# Nixie_Board.net
KiCad netlist of a schematic drawn in EAGLE
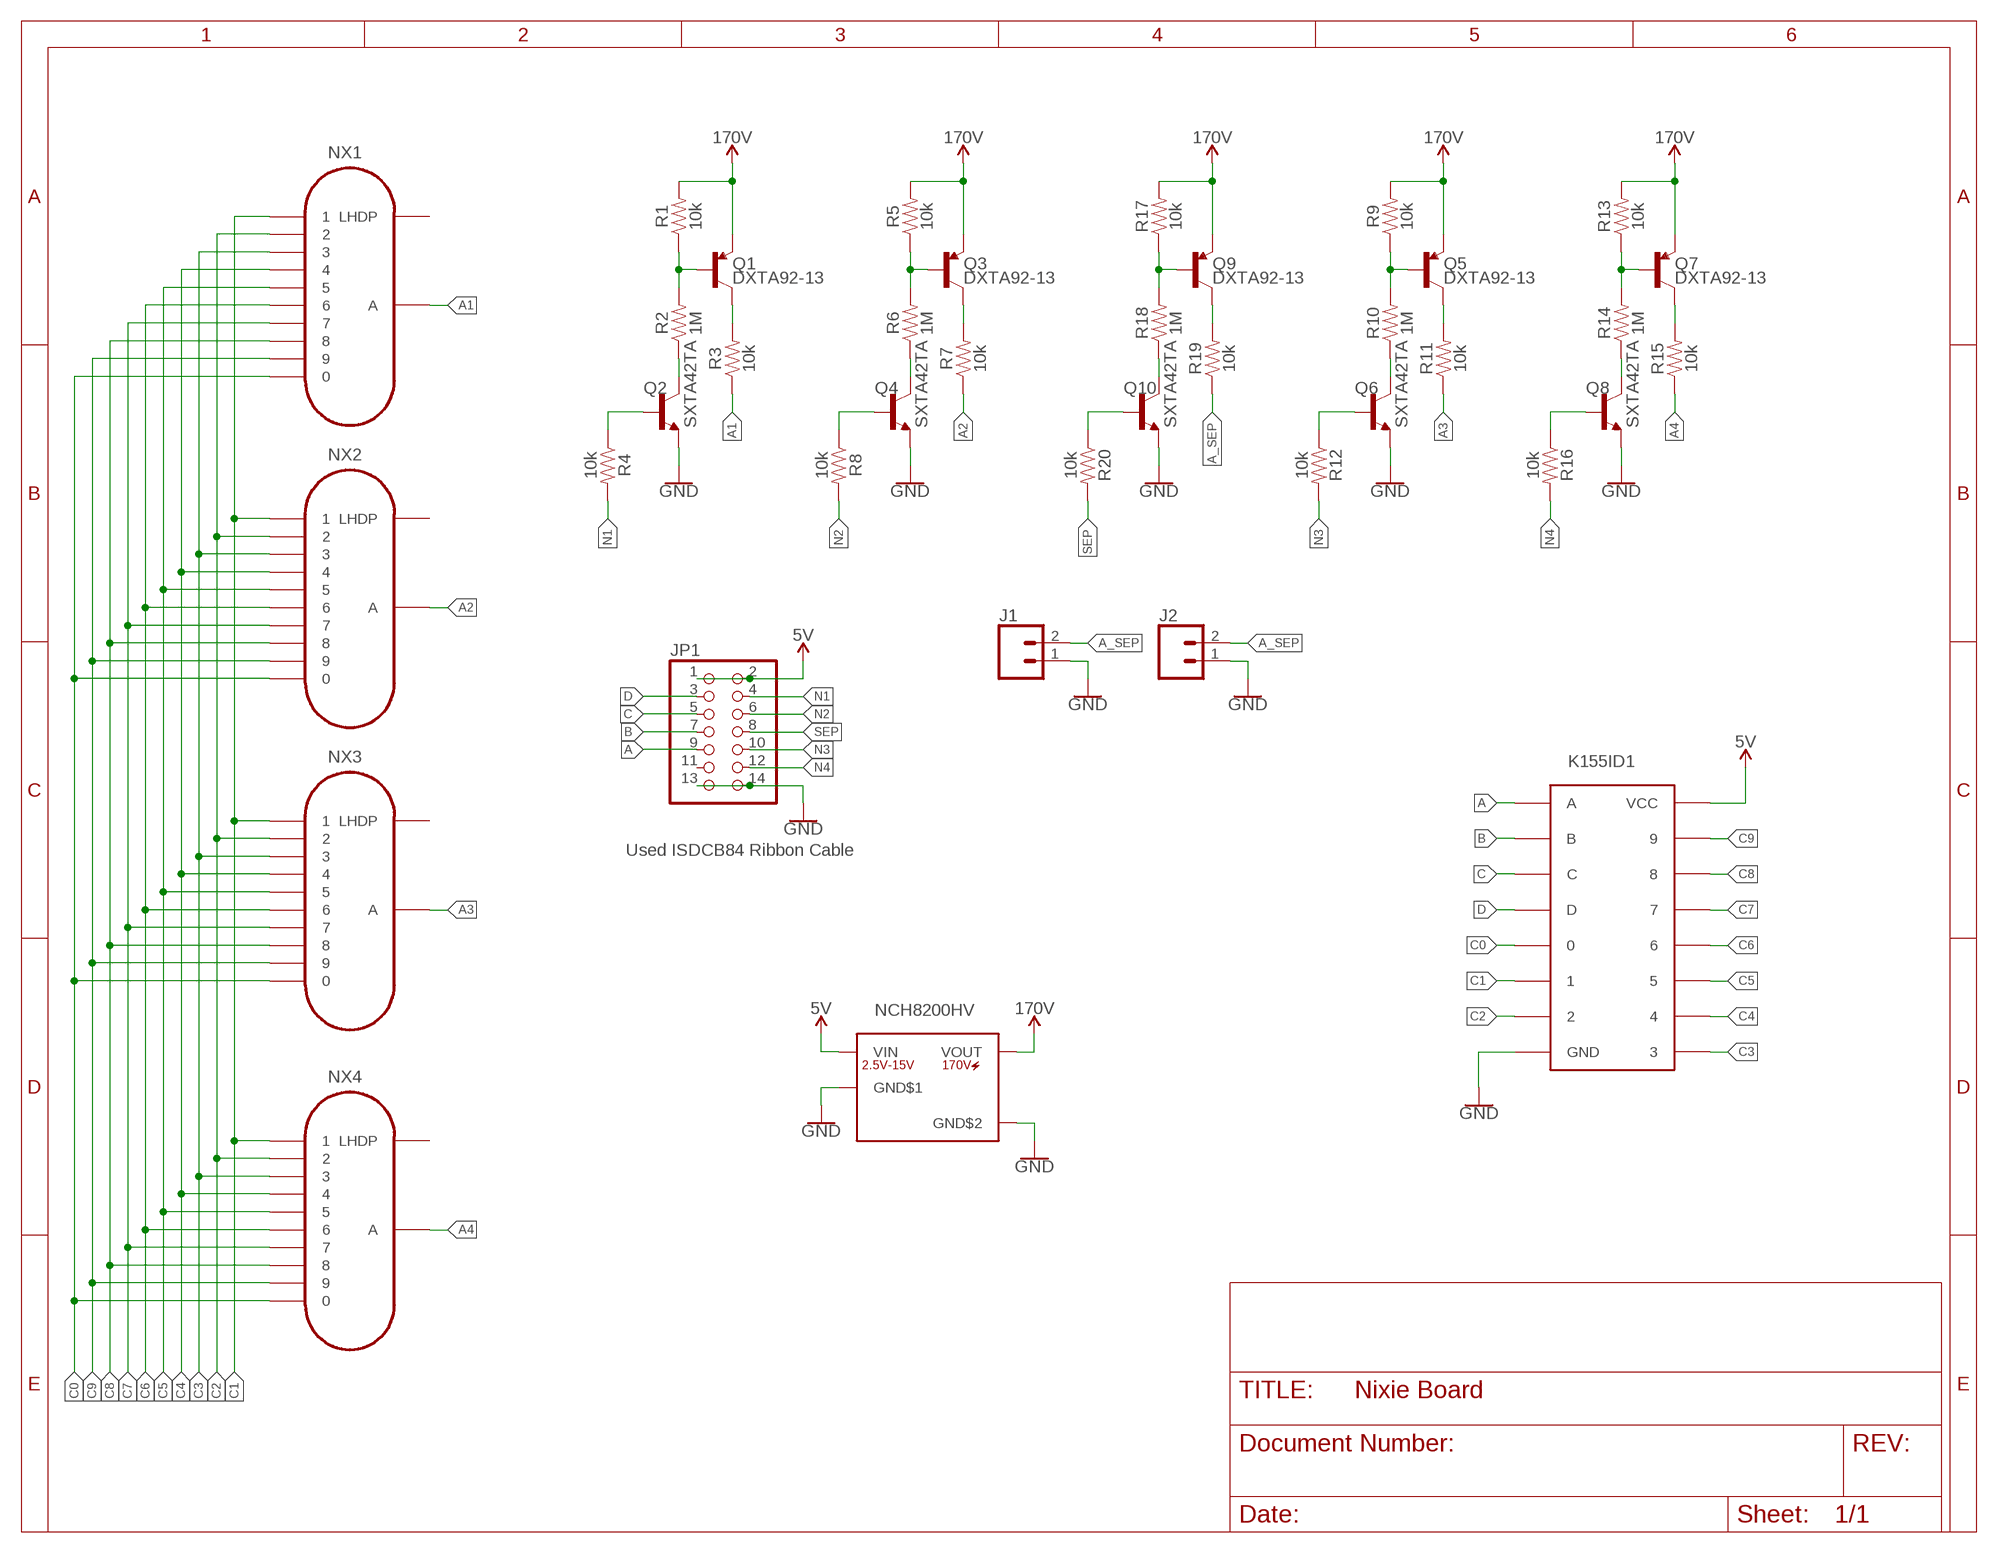
[diagram p0: schematic, sheet 1]

(export (version "E")
  (design (tool "Eeschema 10.0.6"))
  (components
    (comp (ref "J1")
      (value "CONN_02")
      (footprint "eagle-import:1X02")
      (fields (field (name "MPN") "INS-1"))
      (libsource (lib "eagle-import") (part "CONN_02"))
    )
    (comp (ref "J2")
      (value "CONN_02")
      (footprint "eagle-import:1X02")
      (fields (field (name "MPN") "INS-1"))
      (libsource (lib "eagle-import") (part "CONN_02"))
    )
    (comp (ref "JP1")
      (value "PINHD-2X7")
      (footprint "eagle-import:2X07")
      (fields (field (name "MPN") "30314-6002HB"))
      (libsource (lib "eagle-import") (part "PINHD-2X7"))
    )
    (comp (ref "NX1")
      (value "IN-12BNOHOLE")
      (footprint "eagle-import:IN-12-DSUB-NOHOLE")
      (fields (field (name "MPN") "IN-12B"))
      (libsource (lib "eagle-import") (part "IN-12BNOHOLE"))
    )
    (comp (ref "NX2")
      (value "IN-12BNOHOLE")
      (footprint "eagle-import:IN-12-DSUB-NOHOLE")
      (fields (field (name "MPN") "IN-12B"))
      (libsource (lib "eagle-import") (part "IN-12BNOHOLE"))
    )
    (comp (ref "NX3")
      (value "IN-12BNOHOLE")
      (footprint "eagle-import:IN-12-DSUB-NOHOLE")
      (fields (field (name "MPN") "IN-12B"))
      (libsource (lib "eagle-import") (part "IN-12BNOHOLE"))
    )
    (comp (ref "NX4")
      (value "IN-12BNOHOLE")
      (footprint "eagle-import:IN-12-DSUB-NOHOLE")
      (fields (field (name "MPN") "IN-12B"))
      (libsource (lib "eagle-import") (part "IN-12BNOHOLE"))
    )
    (comp (ref "Q1")
      (value "DXTA92-13")
      (footprint "eagle-import:DXTA9213")
      (fields (field (name "MOUSER_PART_NUMBER") "621-DXTA92-13"))
      (libsource (lib "eagle-import") (part "DXTA92-13"))
    )
    (comp (ref "Q2")
      (value "SXTA42TA")
      (footprint "eagle-import:SXTA42TA")
      (fields (field (name "MOUSER_PART_NUMBER") "522-SXTA42TA"))
      (libsource (lib "eagle-import") (part "SXTA42TA"))
    )
    (comp (ref "Q3")
      (value "DXTA92-13")
      (footprint "eagle-import:DXTA9213")
      (fields (field (name "MOUSER_PART_NUMBER") "621-DXTA92-13"))
      (libsource (lib "eagle-import") (part "DXTA92-13"))
    )
    (comp (ref "Q4")
      (value "SXTA42TA")
      (footprint "eagle-import:SXTA42TA")
      (fields (field (name "MOUSER_PART_NUMBER") "522-SXTA42TA"))
      (libsource (lib "eagle-import") (part "SXTA42TA"))
    )
    (comp (ref "Q5")
      (value "DXTA92-13")
      (footprint "eagle-import:DXTA9213")
      (fields (field (name "MOUSER_PART_NUMBER") "621-DXTA92-13"))
      (libsource (lib "eagle-import") (part "DXTA92-13"))
    )
    (comp (ref "Q6")
      (value "SXTA42TA")
      (footprint "eagle-import:SXTA42TA")
      (fields (field (name "MOUSER_PART_NUMBER") "522-SXTA42TA"))
      (libsource (lib "eagle-import") (part "SXTA42TA"))
    )
    (comp (ref "Q7")
      (value "DXTA92-13")
      (footprint "eagle-import:DXTA9213")
      (fields (field (name "MOUSER_PART_NUMBER") "621-DXTA92-13"))
      (libsource (lib "eagle-import") (part "DXTA92-13"))
    )
    (comp (ref "Q8")
      (value "SXTA42TA")
      (footprint "eagle-import:SXTA42TA")
      (fields (field (name "MOUSER_PART_NUMBER") "522-SXTA42TA"))
      (libsource (lib "eagle-import") (part "SXTA42TA"))
    )
    (comp (ref "Q9")
      (value "DXTA92-13")
      (footprint "eagle-import:DXTA9213")
      (fields (field (name "MOUSER_PART_NUMBER") "621-DXTA92-13"))
      (libsource (lib "eagle-import") (part "DXTA92-13"))
    )
    (comp (ref "Q10")
      (value "SXTA42TA")
      (footprint "eagle-import:SXTA42TA")
      (fields (field (name "MOUSER_PART_NUMBER") "522-SXTA42TA"))
      (libsource (lib "eagle-import") (part "SXTA42TA"))
    )
    (comp (ref "R1")
      (value "10k")
      (footprint "eagle-import:0603")
      (fields (field (name "MPN") "ESR03EZPJ103"))
      (libsource (lib "eagle-import") (part "10KOHM-0603-1/10W-1%"))
    )
    (comp (ref "R2")
      (value "1M")
      (footprint "eagle-import:0603")
      (fields (field (name "MPN") "ERJ-3EKF1004V"))
      (libsource (lib "eagle-import") (part "1MOHM-0603-1/4W-5%"))
    )
    (comp (ref "R3")
      (value "10k")
      (footprint "eagle-import:0603")
      (fields (field (name "MPN") "ESR03EZPJ103"))
      (libsource (lib "eagle-import") (part "10KOHM-0603-1/10W-1%"))
    )
    (comp (ref "R4")
      (value "10k")
      (footprint "eagle-import:0603")
      (fields (field (name "MPN") "ESR03EZPJ103"))
      (libsource (lib "eagle-import") (part "10KOHM-0603-1/10W-1%"))
    )
    (comp (ref "R5")
      (value "10k")
      (footprint "eagle-import:0603")
      (fields (field (name "MPN") "ESR03EZPJ103"))
      (libsource (lib "eagle-import") (part "10KOHM-0603-1/10W-1%"))
    )
    (comp (ref "R6")
      (value "1M")
      (footprint "eagle-import:0603")
      (fields (field (name "MPN") "ERJ-3EKF1004V"))
      (libsource (lib "eagle-import") (part "1MOHM-0603-1/4W-5%"))
    )
    (comp (ref "R7")
      (value "10k")
      (footprint "eagle-import:0603")
      (fields (field (name "MPN") "ESR03EZPJ103"))
      (libsource (lib "eagle-import") (part "10KOHM-0603-1/10W-1%"))
    )
    (comp (ref "R8")
      (value "10k")
      (footprint "eagle-import:0603")
      (fields (field (name "MPN") "ESR03EZPJ103"))
      (libsource (lib "eagle-import") (part "10KOHM-0603-1/10W-1%"))
    )
    (comp (ref "R9")
      (value "10k")
      (footprint "eagle-import:0603")
      (fields (field (name "MPN") "ESR03EZPJ103"))
      (libsource (lib "eagle-import") (part "10KOHM-0603-1/10W-1%"))
    )
    (comp (ref "R10")
      (value "1M")
      (footprint "eagle-import:0603")
      (fields (field (name "MPN") "ERJ-3EKF1004V"))
      (libsource (lib "eagle-import") (part "1MOHM-0603-1/4W-5%"))
    )
    (comp (ref "R11")
      (value "10k")
      (footprint "eagle-import:0603")
      (fields (field (name "MPN") "ESR03EZPJ103"))
      (libsource (lib "eagle-import") (part "10KOHM-0603-1/10W-1%"))
    )
    (comp (ref "R12")
      (value "10k")
      (footprint "eagle-import:0603")
      (fields (field (name "MPN") "ESR03EZPJ103"))
      (libsource (lib "eagle-import") (part "10KOHM-0603-1/10W-1%"))
    )
    (comp (ref "R13")
      (value "10k")
      (footprint "eagle-import:0603")
      (fields (field (name "MPN") "ESR03EZPJ103"))
      (libsource (lib "eagle-import") (part "10KOHM-0603-1/10W-1%"))
    )
    (comp (ref "R14")
      (value "1M")
      (footprint "eagle-import:0603")
      (fields (field (name "MPN") "ERJ-3EKF1004V"))
      (libsource (lib "eagle-import") (part "1MOHM-0603-1/4W-5%"))
    )
    (comp (ref "R15")
      (value "10k")
      (footprint "eagle-import:0603")
      (fields (field (name "MPN") "ESR03EZPJ103"))
      (libsource (lib "eagle-import") (part "10KOHM-0603-1/10W-1%"))
    )
    (comp (ref "R16")
      (value "10k")
      (footprint "eagle-import:0603")
      (fields (field (name "MPN") "ESR03EZPJ103"))
      (libsource (lib "eagle-import") (part "10KOHM-0603-1/10W-1%"))
    )
    (comp (ref "R17")
      (value "10k")
      (footprint "eagle-import:0603")
      (fields (field (name "MPN") "ESR03EZPJ103"))
      (libsource (lib "eagle-import") (part "10KOHM-0603-1/10W-1%"))
    )
    (comp (ref "R18")
      (value "1M")
      (footprint "eagle-import:0603")
      (fields (field (name "MPN") "ERJ-3EKF1004V"))
      (libsource (lib "eagle-import") (part "1MOHM-0603-1/4W-5%"))
    )
    (comp (ref "R19")
      (value "10k")
      (footprint "eagle-import:0603")
      (fields (field (name "MPN") "ESR03EZPJ103"))
      (libsource (lib "eagle-import") (part "10KOHM-0603-1/10W-1%"))
    )
    (comp (ref "R20")
      (value "10k")
      (footprint "eagle-import:0603")
      (fields (field (name "MPN") "ESR03EZPJ103"))
      (libsource (lib "eagle-import") (part "10KOHM-0603-1/10W-1%"))
    )
    (comp (ref "U$1")
      (value "K155ID1")
      (footprint "eagle-import:DIP16")
      (libsource (lib "eagle-import") (part "K155ID1"))
    )
    (comp (ref "U$2")
      (value "NCH8200HV")
      (footprint "eagle-import:NCH8200HV")
      (libsource (lib "eagle-import") (part "NCH8200HV"))
    )
  )
  (nets
    (net (code "1") (name "5V") (class "Default")
      (node (ref "JP1") (pin "1") (pinfunction "1_1") (pintype "passive"))
      (node (ref "JP1") (pin "2") (pinfunction "2_2") (pintype "passive"))
      (node (ref "U$1") (pin "5") (pinfunction "VCC_5") (pintype "power_in"))
      (node (ref "U$2") (pin "P$1") (pinfunction "VIN_P$1") (pintype "power_in"))
    )
    (net (code "2") (name "170V") (class "Default")
      (node (ref "Q1") (pin "3") (pinfunction "E_3") (pintype "passive"))
      (node (ref "Q3") (pin "3") (pinfunction "E_3") (pintype "passive"))
      (node (ref "Q5") (pin "3") (pinfunction "E_3") (pintype "passive"))
      (node (ref "Q7") (pin "3") (pinfunction "E_3") (pintype "passive"))
      (node (ref "Q9") (pin "3") (pinfunction "E_3") (pintype "passive"))
      (node (ref "R1") (pin "2") (pinfunction "2_2") (pintype "passive"))
      (node (ref "R13") (pin "2") (pinfunction "2_2") (pintype "passive"))
      (node (ref "R17") (pin "2") (pinfunction "2_2") (pintype "passive"))
      (node (ref "R5") (pin "2") (pinfunction "2_2") (pintype "passive"))
      (node (ref "R9") (pin "2") (pinfunction "2_2") (pintype "passive"))
      (node (ref "U$2") (pin "P$4") (pinfunction "VOUT_P$4") (pintype "power_in"))
    )
    (net (code "3") (name "A") (class "Default")
      (node (ref "JP1") (pin "9") (pinfunction "9_9") (pintype "passive"))
      (node (ref "U$1") (pin "3") (pinfunction "A_3") (pintype "input"))
    )
    (net (code "4") (name "A1") (class "Default")
      (node (ref "NX1") (pin "A") (pinfunction "A_A") (pintype "bidirectional"))
      (node (ref "R3") (pin "1") (pinfunction "1_1") (pintype "passive"))
    )
    (net (code "5") (name "A2") (class "Default")
      (node (ref "NX2") (pin "A") (pinfunction "A_A") (pintype "bidirectional"))
      (node (ref "R7") (pin "1") (pinfunction "1_1") (pintype "passive"))
    )
    (net (code "6") (name "A3") (class "Default")
      (node (ref "NX3") (pin "A") (pinfunction "A_A") (pintype "bidirectional"))
      (node (ref "R11") (pin "1") (pinfunction "1_1") (pintype "passive"))
    )
    (net (code "7") (name "A4") (class "Default")
      (node (ref "NX4") (pin "A") (pinfunction "A_A") (pintype "bidirectional"))
      (node (ref "R15") (pin "1") (pinfunction "1_1") (pintype "passive"))
    )
    (net (code "8") (name "A_SEP") (class "Default")
      (node (ref "J1") (pin "2") (pinfunction "2_2") (pintype "passive"))
      (node (ref "J2") (pin "2") (pinfunction "2_2") (pintype "passive"))
      (node (ref "R19") (pin "1") (pinfunction "1_1") (pintype "passive"))
    )
    (net (code "9") (name "B") (class "Default")
      (node (ref "JP1") (pin "7") (pinfunction "7_7") (pintype "passive"))
      (node (ref "U$1") (pin "6") (pinfunction "B_6") (pintype "input"))
    )
    (net (code "10") (name "C") (class "Default")
      (node (ref "JP1") (pin "5") (pinfunction "5_5") (pintype "passive"))
      (node (ref "U$1") (pin "7") (pinfunction "C_7") (pintype "input"))
    )
    (net (code "11") (name "C0") (class "Default")
      (node (ref "NX1") (pin "0") (pinfunction "0_0") (pintype "bidirectional"))
      (node (ref "NX2") (pin "0") (pinfunction "0_0") (pintype "bidirectional"))
      (node (ref "NX3") (pin "0") (pinfunction "0_0") (pintype "bidirectional"))
      (node (ref "NX4") (pin "0") (pinfunction "0_0") (pintype "bidirectional"))
      (node (ref "U$1") (pin "16") (pinfunction "0_16") (pintype "output"))
    )
    (net (code "12") (name "C1") (class "Default")
      (node (ref "NX1") (pin "1") (pinfunction "1_1") (pintype "bidirectional"))
      (node (ref "NX2") (pin "1") (pinfunction "1_1") (pintype "bidirectional"))
      (node (ref "NX3") (pin "1") (pinfunction "1_1") (pintype "bidirectional"))
      (node (ref "NX4") (pin "1") (pinfunction "1_1") (pintype "bidirectional"))
      (node (ref "U$1") (pin "15") (pinfunction "1_15") (pintype "output"))
    )
    (net (code "13") (name "C2") (class "Default")
      (node (ref "NX1") (pin "2") (pinfunction "2_2") (pintype "bidirectional"))
      (node (ref "NX2") (pin "2") (pinfunction "2_2") (pintype "bidirectional"))
      (node (ref "NX3") (pin "2") (pinfunction "2_2") (pintype "bidirectional"))
      (node (ref "NX4") (pin "2") (pinfunction "2_2") (pintype "bidirectional"))
      (node (ref "U$1") (pin "8") (pinfunction "2_8") (pintype "output"))
    )
    (net (code "14") (name "C3") (class "Default")
      (node (ref "NX1") (pin "3") (pinfunction "3_3") (pintype "bidirectional"))
      (node (ref "NX2") (pin "3") (pinfunction "3_3") (pintype "bidirectional"))
      (node (ref "NX3") (pin "3") (pinfunction "3_3") (pintype "bidirectional"))
      (node (ref "NX4") (pin "3") (pinfunction "3_3") (pintype "bidirectional"))
      (node (ref "U$1") (pin "9") (pinfunction "3_9") (pintype "output"))
    )
    (net (code "15") (name "C4") (class "Default")
      (node (ref "NX1") (pin "4") (pinfunction "4_4") (pintype "bidirectional"))
      (node (ref "NX2") (pin "4") (pinfunction "4_4") (pintype "bidirectional"))
      (node (ref "NX3") (pin "4") (pinfunction "4_4") (pintype "bidirectional"))
      (node (ref "NX4") (pin "4") (pinfunction "4_4") (pintype "bidirectional"))
      (node (ref "U$1") (pin "13") (pinfunction "4_13") (pintype "output"))
    )
    (net (code "16") (name "C5") (class "Default")
      (node (ref "NX1") (pin "5") (pinfunction "5_5") (pintype "bidirectional"))
      (node (ref "NX2") (pin "5") (pinfunction "5_5") (pintype "bidirectional"))
      (node (ref "NX3") (pin "5") (pinfunction "5_5") (pintype "bidirectional"))
      (node (ref "NX4") (pin "5") (pinfunction "5_5") (pintype "bidirectional"))
      (node (ref "U$1") (pin "14") (pinfunction "5_14") (pintype "output"))
    )
    (net (code "17") (name "C6") (class "Default")
      (node (ref "NX1") (pin "6") (pinfunction "6_6") (pintype "bidirectional"))
      (node (ref "NX2") (pin "6") (pinfunction "6_6") (pintype "bidirectional"))
      (node (ref "NX3") (pin "6") (pinfunction "6_6") (pintype "bidirectional"))
      (node (ref "NX4") (pin "6") (pinfunction "6_6") (pintype "bidirectional"))
      (node (ref "U$1") (pin "11") (pinfunction "6_11") (pintype "output"))
    )
    (net (code "18") (name "C7") (class "Default")
      (node (ref "NX1") (pin "7") (pinfunction "7_7") (pintype "bidirectional"))
      (node (ref "NX2") (pin "7") (pinfunction "7_7") (pintype "bidirectional"))
      (node (ref "NX3") (pin "7") (pinfunction "7_7") (pintype "bidirectional"))
      (node (ref "NX4") (pin "7") (pinfunction "7_7") (pintype "bidirectional"))
      (node (ref "U$1") (pin "10") (pinfunction "7_10") (pintype "output"))
    )
    (net (code "19") (name "C8") (class "Default")
      (node (ref "NX1") (pin "8") (pinfunction "8_8") (pintype "bidirectional"))
      (node (ref "NX2") (pin "8") (pinfunction "8_8") (pintype "bidirectional"))
      (node (ref "NX3") (pin "8") (pinfunction "8_8") (pintype "bidirectional"))
      (node (ref "NX4") (pin "8") (pinfunction "8_8") (pintype "bidirectional"))
      (node (ref "U$1") (pin "1") (pinfunction "8_1") (pintype "output"))
    )
    (net (code "20") (name "C9") (class "Default")
      (node (ref "NX1") (pin "9") (pinfunction "9_9") (pintype "bidirectional"))
      (node (ref "NX2") (pin "9") (pinfunction "9_9") (pintype "bidirectional"))
      (node (ref "NX3") (pin "9") (pinfunction "9_9") (pintype "bidirectional"))
      (node (ref "NX4") (pin "9") (pinfunction "9_9") (pintype "bidirectional"))
      (node (ref "U$1") (pin "2") (pinfunction "9_2") (pintype "output"))
    )
    (net (code "21") (name "D") (class "Default")
      (node (ref "JP1") (pin "3") (pinfunction "3_3") (pintype "passive"))
      (node (ref "U$1") (pin "4") (pinfunction "D_4") (pintype "input"))
    )
    (net (code "22") (name "GND") (class "Default")
      (node (ref "J1") (pin "1") (pinfunction "1_1") (pintype "passive"))
      (node (ref "J2") (pin "1") (pinfunction "1_1") (pintype "passive"))
      (node (ref "JP1") (pin "13") (pinfunction "13_13") (pintype "passive"))
      (node (ref "JP1") (pin "14") (pinfunction "14_14") (pintype "passive"))
      (node (ref "Q10") (pin "3") (pinfunction "E_3") (pintype "passive"))
      (node (ref "Q2") (pin "3") (pinfunction "E_3") (pintype "passive"))
      (node (ref "Q4") (pin "3") (pinfunction "E_3") (pintype "passive"))
      (node (ref "Q6") (pin "3") (pinfunction "E_3") (pintype "passive"))
      (node (ref "Q8") (pin "3") (pinfunction "E_3") (pintype "passive"))
      (node (ref "U$1") (pin "12") (pinfunction "GND_12") (pintype "power_in"))
      (node (ref "U$2") (pin "P$2") (pinfunction "GND$1_P$2") (pintype "power_in"))
      (node (ref "U$2") (pin "P$3") (pinfunction "GND$2_P$3") (pintype "power_in"))
    )
    (net (code "23") (name "N1") (class "Default")
      (node (ref "JP1") (pin "4") (pinfunction "4_4") (pintype "passive"))
      (node (ref "R4") (pin "2") (pinfunction "2_2") (pintype "passive"))
    )
    (net (code "24") (name "N2") (class "Default")
      (node (ref "JP1") (pin "6") (pinfunction "6_6") (pintype "passive"))
      (node (ref "R8") (pin "2") (pinfunction "2_2") (pintype "passive"))
    )
    (net (code "25") (name "N3") (class "Default")
      (node (ref "JP1") (pin "10") (pinfunction "10_10") (pintype "passive"))
      (node (ref "R12") (pin "2") (pinfunction "2_2") (pintype "passive"))
    )
    (net (code "26") (name "N4") (class "Default")
      (node (ref "JP1") (pin "12") (pinfunction "12_12") (pintype "passive"))
      (node (ref "R16") (pin "2") (pinfunction "2_2") (pintype "passive"))
    )
    (net (code "27") (name "Net-(Q1-B)") (class "Default")
      (node (ref "Q1") (pin "1") (pinfunction "B_1") (pintype "passive"))
      (node (ref "R1") (pin "1") (pinfunction "1_1") (pintype "passive"))
      (node (ref "R2") (pin "2") (pinfunction "2_2") (pintype "passive"))
    )
    (net (code "28") (name "Net-(Q1-C)") (class "Default")
      (node (ref "Q1") (pin "2") (pinfunction "C_2") (pintype "passive"))
      (node (ref "R3") (pin "2") (pinfunction "2_2") (pintype "passive"))
    )
    (net (code "29") (name "Net-(Q2-B)") (class "Default")
      (node (ref "Q2") (pin "1") (pinfunction "B_1") (pintype "passive"))
      (node (ref "R4") (pin "1") (pinfunction "1_1") (pintype "passive"))
    )
    (net (code "30") (name "Net-(Q2-C)") (class "Default")
      (node (ref "Q2") (pin "2") (pinfunction "C_2") (pintype "passive"))
      (node (ref "R2") (pin "1") (pinfunction "1_1") (pintype "passive"))
    )
    (net (code "31") (name "Net-(Q3-B)") (class "Default")
      (node (ref "Q3") (pin "1") (pinfunction "B_1") (pintype "passive"))
      (node (ref "R5") (pin "1") (pinfunction "1_1") (pintype "passive"))
      (node (ref "R6") (pin "2") (pinfunction "2_2") (pintype "passive"))
    )
    (net (code "32") (name "Net-(Q3-C)") (class "Default")
      (node (ref "Q3") (pin "2") (pinfunction "C_2") (pintype "passive"))
      (node (ref "R7") (pin "2") (pinfunction "2_2") (pintype "passive"))
    )
    (net (code "33") (name "Net-(Q4-B)") (class "Default")
      (node (ref "Q4") (pin "1") (pinfunction "B_1") (pintype "passive"))
      (node (ref "R8") (pin "1") (pinfunction "1_1") (pintype "passive"))
    )
    (net (code "34") (name "Net-(Q4-C)") (class "Default")
      (node (ref "Q4") (pin "2") (pinfunction "C_2") (pintype "passive"))
      (node (ref "R6") (pin "1") (pinfunction "1_1") (pintype "passive"))
    )
    (net (code "35") (name "Net-(Q5-B)") (class "Default")
      (node (ref "Q5") (pin "1") (pinfunction "B_1") (pintype "passive"))
      (node (ref "R10") (pin "2") (pinfunction "2_2") (pintype "passive"))
      (node (ref "R9") (pin "1") (pinfunction "1_1") (pintype "passive"))
    )
    (net (code "36") (name "Net-(Q5-C)") (class "Default")
      (node (ref "Q5") (pin "2") (pinfunction "C_2") (pintype "passive"))
      (node (ref "R11") (pin "2") (pinfunction "2_2") (pintype "passive"))
    )
    (net (code "37") (name "Net-(Q6-B)") (class "Default")
      (node (ref "Q6") (pin "1") (pinfunction "B_1") (pintype "passive"))
      (node (ref "R12") (pin "1") (pinfunction "1_1") (pintype "passive"))
    )
    (net (code "38") (name "Net-(Q6-C)") (class "Default")
      (node (ref "Q6") (pin "2") (pinfunction "C_2") (pintype "passive"))
      (node (ref "R10") (pin "1") (pinfunction "1_1") (pintype "passive"))
    )
    (net (code "39") (name "Net-(Q7-B)") (class "Default")
      (node (ref "Q7") (pin "1") (pinfunction "B_1") (pintype "passive"))
      (node (ref "R13") (pin "1") (pinfunction "1_1") (pintype "passive"))
      (node (ref "R14") (pin "2") (pinfunction "2_2") (pintype "passive"))
    )
    (net (code "40") (name "Net-(Q7-C)") (class "Default")
      (node (ref "Q7") (pin "2") (pinfunction "C_2") (pintype "passive"))
      (node (ref "R15") (pin "2") (pinfunction "2_2") (pintype "passive"))
    )
    (net (code "41") (name "Net-(Q8-B)") (class "Default")
      (node (ref "Q8") (pin "1") (pinfunction "B_1") (pintype "passive"))
      (node (ref "R16") (pin "1") (pinfunction "1_1") (pintype "passive"))
    )
    (net (code "42") (name "Net-(Q8-C)") (class "Default")
      (node (ref "Q8") (pin "2") (pinfunction "C_2") (pintype "passive"))
      (node (ref "R14") (pin "1") (pinfunction "1_1") (pintype "passive"))
    )
    (net (code "43") (name "Net-(Q9-B)") (class "Default")
      (node (ref "Q9") (pin "1") (pinfunction "B_1") (pintype "passive"))
      (node (ref "R17") (pin "1") (pinfunction "1_1") (pintype "passive"))
      (node (ref "R18") (pin "2") (pinfunction "2_2") (pintype "passive"))
    )
    (net (code "44") (name "Net-(Q9-C)") (class "Default")
      (node (ref "Q9") (pin "2") (pinfunction "C_2") (pintype "passive"))
      (node (ref "R19") (pin "2") (pinfunction "2_2") (pintype "passive"))
    )
    (net (code "45") (name "Net-(Q10-B)") (class "Default")
      (node (ref "Q10") (pin "1") (pinfunction "B_1") (pintype "passive"))
      (node (ref "R20") (pin "1") (pinfunction "1_1") (pintype "passive"))
    )
    (net (code "46") (name "Net-(Q10-C)") (class "Default")
      (node (ref "Q10") (pin "2") (pinfunction "C_2") (pintype "passive"))
      (node (ref "R18") (pin "1") (pinfunction "1_1") (pintype "passive"))
    )
    (net (code "47") (name "SEP") (class "Default")
      (node (ref "JP1") (pin "8") (pinfunction "8_8") (pintype "passive"))
      (node (ref "R20") (pin "2") (pinfunction "2_2") (pintype "passive"))
    )
    (net (code "48") (name "unconnected-(JP1-Pad11)") (class "Default")
      (node (ref "JP1") (pin "11") (pinfunction "11_11") (pintype "passive"))
    )
    (net (code "49") (name "unconnected-(NX1-PadLHDP)") (class "Default")
      (node (ref "NX1") (pin "LHDP") (pinfunction "LHDP_LHDP") (pintype "bidirectional"))
    )
    (net (code "50") (name "unconnected-(NX2-PadLHDP)") (class "Default")
      (node (ref "NX2") (pin "LHDP") (pinfunction "LHDP_LHDP") (pintype "bidirectional"))
    )
    (net (code "51") (name "unconnected-(NX3-PadLHDP)") (class "Default")
      (node (ref "NX3") (pin "LHDP") (pinfunction "LHDP_LHDP") (pintype "bidirectional"))
    )
    (net (code "52") (name "unconnected-(NX4-PadLHDP)") (class "Default")
      (node (ref "NX4") (pin "LHDP") (pinfunction "LHDP_LHDP") (pintype "bidirectional"))
    )
  )
)
